# Calibration.net
KiCad netlist of a schematic drawn in EAGLE
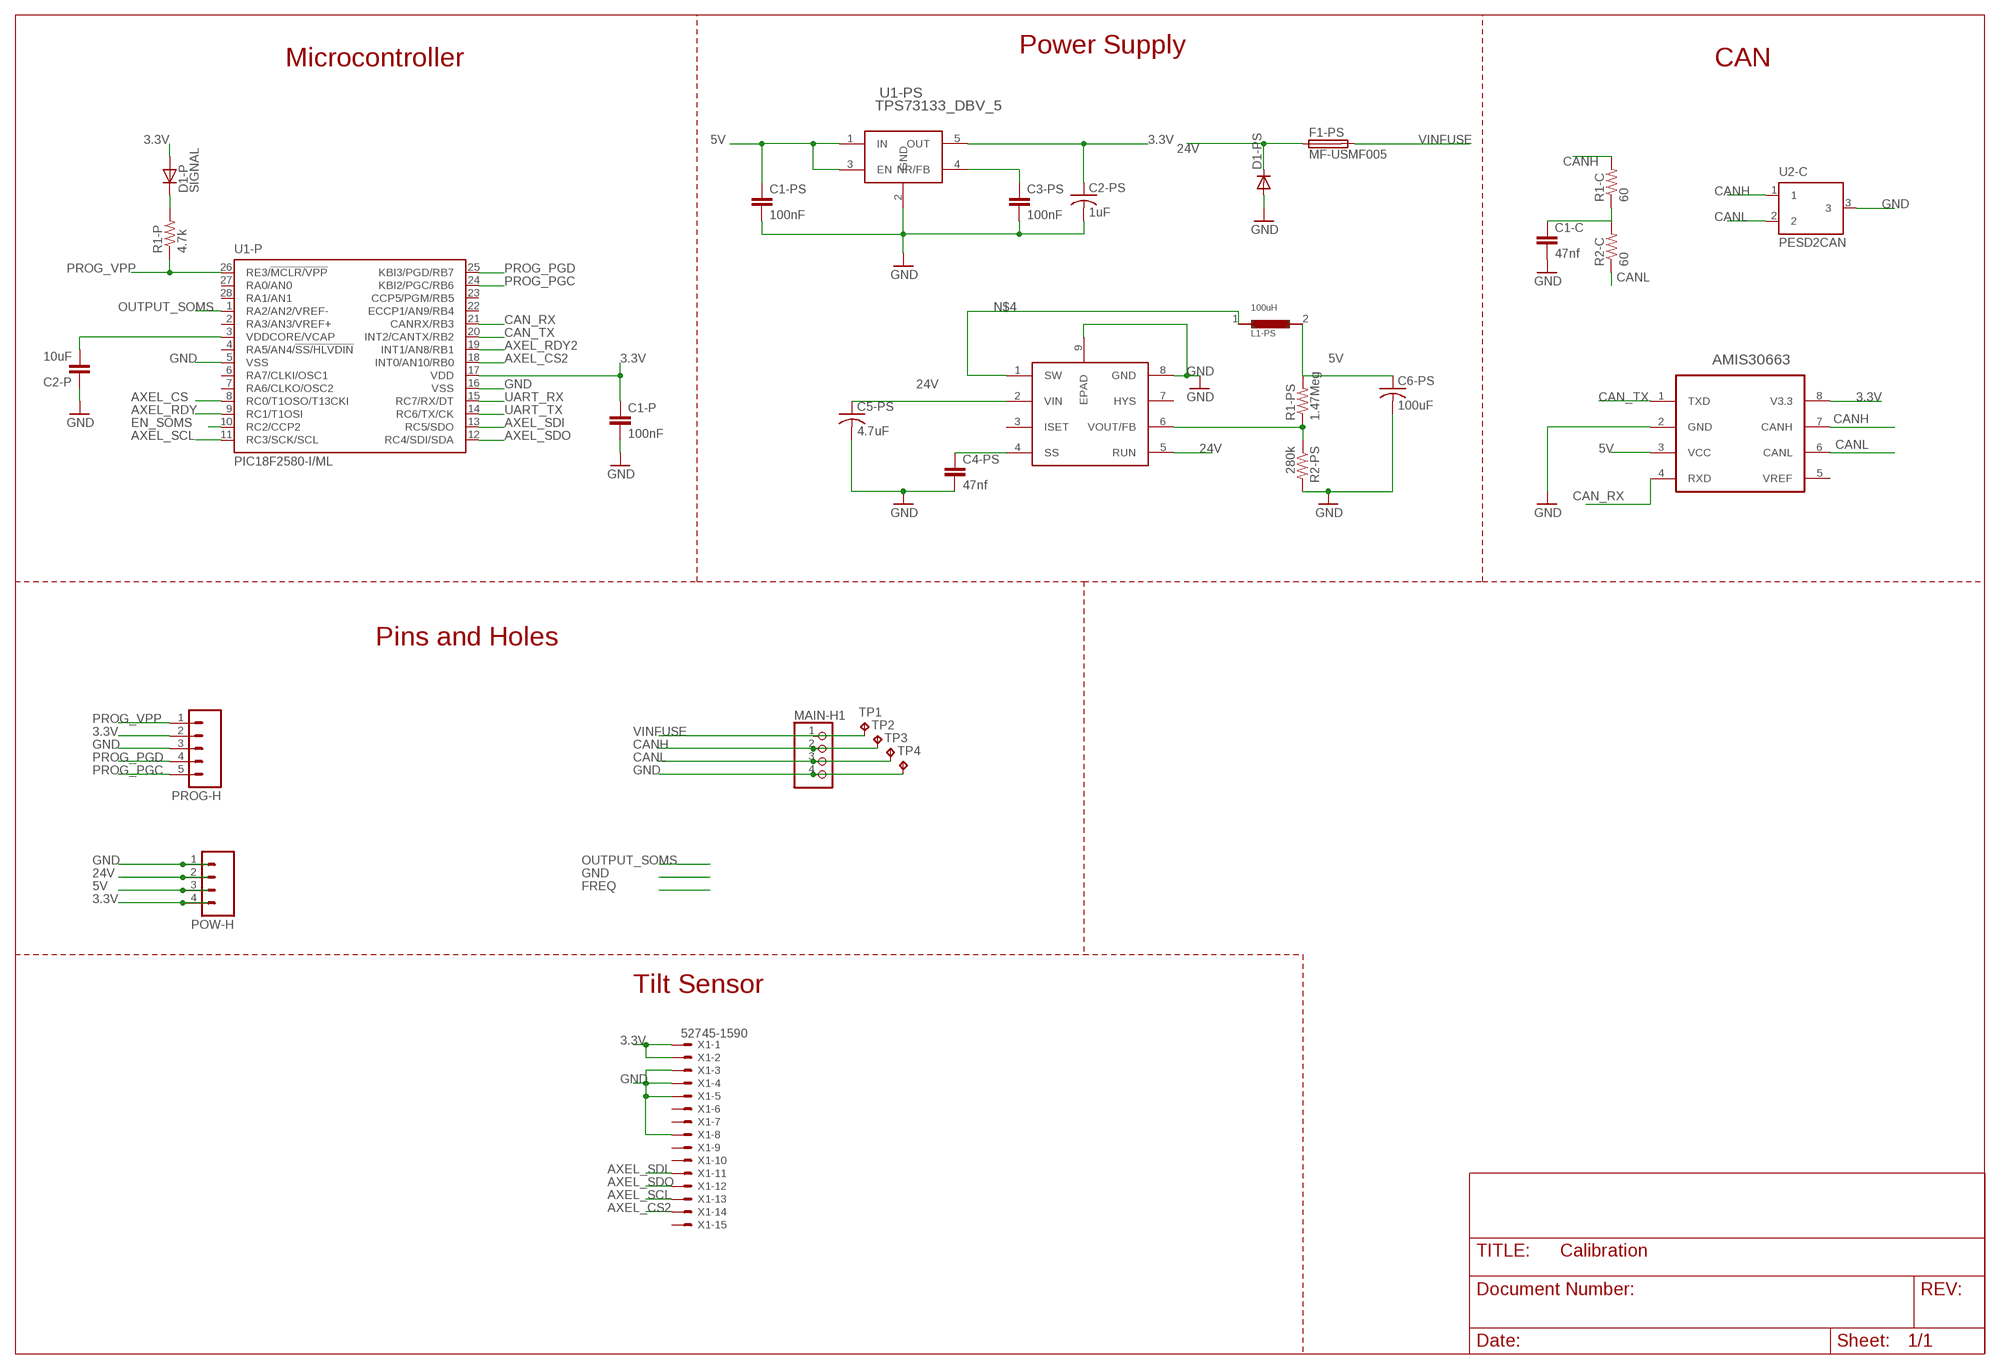
[diagram p0: schematic, sheet 1]

(export (version "E")
  (design (tool "Eeschema 10.0.6"))
  (components
    (comp (ref "C1-C")
      (value "47nf")
      (footprint "eagle-import:C0805")
      (libsource (lib "eagle-import") (part "C-EUC0805"))
    )
    (comp (ref "C1-P")
      (value "100nF")
      (footprint "eagle-import:C0603")
      (libsource (lib "eagle-import") (part "resistor_C-EUC0603"))
    )
    (comp (ref "C1-PS")
      (value "100nF")
      (footprint "eagle-import:C0603")
      (libsource (lib "eagle-import") (part "C-EUC0603"))
    )
    (comp (ref "C2-P")
      (value "10uF")
      (footprint "eagle-import:C0603")
      (libsource (lib "eagle-import") (part "C-EUC0603"))
    )
    (comp (ref "C2-PS")
      (value "1uF")
      (footprint "eagle-import:C0402")
      (libsource (lib "eagle-import") (part "C-USC0402"))
    )
    (comp (ref "C3-PS")
      (value "100nF")
      (footprint "eagle-import:C0603")
      (libsource (lib "eagle-import") (part "C-EUC0603"))
    )
    (comp (ref "C4-PS")
      (value "47nf")
      (footprint "eagle-import:C0805")
      (libsource (lib "eagle-import") (part "C-EUC0805"))
    )
    (comp (ref "C5-PS")
      (value "4.7uF")
      (footprint "eagle-import:C1206K")
      (libsource (lib "eagle-import") (part "C-USC1206K"))
    )
    (comp (ref "C6-PS")
      (value "100uF")
      (footprint "eagle-import:C1210K")
      (libsource (lib "eagle-import") (part "C-USC1210K"))
    )
    (comp (ref "D1-P")
      (value "SIGNAL")
      (footprint "eagle-import:DIODE-0603")
      (libsource (lib "eagle-import") (part "DIODE0603"))
    )
    (comp (ref "D1-PS")
      (value "DIODE-DO-214AC")
      (footprint "eagle-import:DO-214AC")
      (libsource (lib "eagle-import") (part "DIODE-DO-214AC"))
    )
    (comp (ref "F1-PS")
      (value "MF-USMF005")
      (footprint "eagle-import:1210")
      (libsource (lib "eagle-import") (part "MF-USMF075"))
    )
    (comp (ref "L1-PS")
      (value "100uH")
      (footprint "eagle-import:1210")
      (libsource (lib "eagle-import") (part "LQH32PN101MN0L"))
    )
    (comp (ref "MAIN-H1")
      (value "PINHD-1X04_2.54")
      (footprint "eagle-import:1X04")
      (libsource (lib "eagle-import") (part "PINHD-1X04_2.54"))
    )
    (comp (ref "POW-H")
      (value "M041X04_NO_SILK")
      (footprint "eagle-import:1X04_NO_SILK")
      (libsource (lib "eagle-import") (part "M041X04_NO_SILK"))
    )
    (comp (ref "PROG-H")
      (value "M05PTH")
      (footprint "eagle-import:1X05")
      (libsource (lib "eagle-import") (part "M05PTH"))
    )
    (comp (ref "R1-C")
      (value "60")
      (footprint "eagle-import:R0805")
      (libsource (lib "eagle-import") (part "R-US_R0805"))
    )
    (comp (ref "R1-P")
      (value "4.7k")
      (footprint "eagle-import:R0603")
      (libsource (lib "eagle-import") (part "resistor_R-US_R0603"))
    )
    (comp (ref "R1-PS")
      (value "1.47Meg")
      (footprint "eagle-import:R0805")
      (libsource (lib "eagle-import") (part "R-US_R0805"))
    )
    (comp (ref "R2-C")
      (value "60")
      (footprint "eagle-import:R0805")
      (libsource (lib "eagle-import") (part "R-US_R0805"))
    )
    (comp (ref "R2-PS")
      (value "280k")
      (footprint "eagle-import:R0805")
      (libsource (lib "eagle-import") (part "R-US_R0805"))
    )
    (comp (ref "TP1")
      (value "TPTP10SQ")
      (footprint "eagle-import:TP10SQ")
      (libsource (lib "eagle-import") (part "TPTP10SQ"))
    )
    (comp (ref "TP2")
      (value "TPTP10SQ")
      (footprint "eagle-import:TP10SQ")
      (libsource (lib "eagle-import") (part "TPTP10SQ"))
    )
    (comp (ref "TP3")
      (value "TPTP10SQ")
      (footprint "eagle-import:TP10SQ")
      (libsource (lib "eagle-import") (part "TPTP10SQ"))
    )
    (comp (ref "TP4")
      (value "TPTP10SQ")
      (footprint "eagle-import:TP10SQ")
      (libsource (lib "eagle-import") (part "TPTP10SQ"))
    )
    (comp (ref "U1-P")
      (value "PIC18F2580-I/ML")
      (footprint "eagle-import:QFN28-ML_6X6MM")
      (fields (field (name "MF") "MICROCHIP"))
      (libsource (lib "eagle-import") (part "PIC18F280-I/ML5"))
    )
    (comp (ref "U1-PS")
      (value "TPS73133_DBV_5")
      (footprint "eagle-import:DBV5")
      (fields
        (field (name "GENERIC_PART_NUMBER") "TPS73133")
        (field (name "MANUFACTURER") "Texas Instruments")
        (field (name "MANUFACTURER_PART_NUMBER") "tps73133_dbv_5")
      )
      (libsource (lib "eagle-import") (part "TPS73133_DBV_5"))
    )
    (comp (ref "U2")
      (value "AMIS30663CAN")
      (footprint "eagle-import:SOIC8")
      (fields (field (name "MPN") "AMIS30663"))
      (libsource (lib "eagle-import") (part "AMIS30663CAN"))
    )
    (comp (ref "U2-C")
      (value "PESD2CAN")
      (footprint "eagle-import:SOT23")
      (libsource (lib "eagle-import") (part "PESD2CAN"))
    )
    (comp (ref "U2-PS")
      (value "LTC3631-5")
      (footprint "eagle-import:MSOP8E")
      (libsource (lib "eagle-import") (part "LTC3631"))
    )
    (comp (ref "X1")
      (value "52745-1590")
      (footprint "eagle-import:52745-1590")
      (fields (field (name "MF") "MOLEX"))
      (libsource (lib "eagle-import") (part "52745-1590"))
    )
  )
  (nets
    (net (code "1") (name "/3.3V") (class "Default")
      (node (ref "C1-P") (pin "1") (pinfunction "1_1") (pintype "passive"))
      (node (ref "C2-PS") (pin "1") (pinfunction "1_1") (pintype "passive"))
      (node (ref "D1-P") (pin "A") (pinfunction "A_A") (pintype "passive"))
      (node (ref "POW-H") (pin "4") (pinfunction "4_4") (pintype "passive"))
      (node (ref "PROG-H") (pin "2") (pinfunction "2_2") (pintype "passive"))
      (node (ref "U1-P") (pin "17") (pinfunction "VDD_17") (pintype "power_in"))
      (node (ref "U1-PS") (pin "5") (pinfunction "OUT_5") (pintype "output"))
      (node (ref "U2") (pin "8") (pinfunction "V3.3_8") (pintype "bidirectional"))
      (node (ref "X1") (pin "1") (pinfunction "S_1") (pintype "passive"))
      (node (ref "X1") (pin "2") (pinfunction "S_2") (pintype "passive"))
    )
    (net (code "2") (name "/5V") (class "Default")
      (node (ref "C1-PS") (pin "1") (pinfunction "1_1") (pintype "passive"))
      (node (ref "C6-PS") (pin "1") (pinfunction "1_1") (pintype "passive"))
      (node (ref "L1-PS") (pin "2") (pinfunction "2_2") (pintype "bidirectional"))
      (node (ref "POW-H") (pin "3") (pinfunction "3_3") (pintype "passive"))
      (node (ref "R1-PS") (pin "2") (pinfunction "2_2") (pintype "passive"))
      (node (ref "U1-PS") (pin "1") (pinfunction "IN_1") (pintype "input"))
      (node (ref "U1-PS") (pin "3") (pinfunction "EN_3") (pintype "passive"))
      (node (ref "U2") (pin "3") (pinfunction "VCC_3") (pintype "bidirectional"))
    )
    (net (code "3") (name "/24V") (class "Default")
      (node (ref "C5-PS") (pin "1") (pinfunction "1_1") (pintype "passive"))
      (node (ref "D1-PS") (pin "1") (pinfunction "C_1") (pintype "passive"))
      (node (ref "F1-PS") (pin "1") (pinfunction "1_1") (pintype "passive"))
      (node (ref "POW-H") (pin "2") (pinfunction "2_2") (pintype "passive"))
      (node (ref "U2-PS") (pin "2") (pinfunction "VIN_2") (pintype "bidirectional"))
      (node (ref "U2-PS") (pin "5") (pinfunction "RUN_5") (pintype "bidirectional"))
    )
    (net (code "4") (name "/AXEL_CS") (class "Default")
      (node (ref "U1-P") (pin "8") (pinfunction "RC0/T1OSO/T13CKI_8") (pintype "bidirectional"))
    )
    (net (code "5") (name "/AXEL_CS2") (class "Default")
      (node (ref "U1-P") (pin "18") (pinfunction "INT0/AN10/RB0_18") (pintype "bidirectional"))
      (node (ref "X1") (pin "14") (pinfunction "S_14") (pintype "passive"))
    )
    (net (code "6") (name "/AXEL_RDY") (class "Default")
      (node (ref "U1-P") (pin "9") (pinfunction "RC1/T1OSI_9") (pintype "bidirectional"))
    )
    (net (code "7") (name "/AXEL_RDY2") (class "Default")
      (node (ref "U1-P") (pin "19") (pinfunction "INT1/AN8/RB1_19") (pintype "bidirectional"))
    )
    (net (code "8") (name "/AXEL_SCL") (class "Default")
      (node (ref "U1-P") (pin "11") (pinfunction "RC3/SCK/SCL_11") (pintype "bidirectional"))
      (node (ref "X1") (pin "13") (pinfunction "S_13") (pintype "passive"))
    )
    (net (code "9") (name "/AXEL_SDI") (class "Default")
      (node (ref "U1-P") (pin "13") (pinfunction "RC5/SDO_13") (pintype "bidirectional"))
      (node (ref "X1") (pin "11") (pinfunction "S_11") (pintype "passive"))
    )
    (net (code "10") (name "/AXEL_SDO") (class "Default")
      (node (ref "U1-P") (pin "12") (pinfunction "RC4/SDI/SDA_12") (pintype "bidirectional"))
      (node (ref "X1") (pin "12") (pinfunction "S_12") (pintype "passive"))
    )
    (net (code "11") (name "/CANH") (class "Default")
      (node (ref "MAIN-H1") (pin "2") (pinfunction "2_2") (pintype "passive"))
      (node (ref "R1-C") (pin "2") (pinfunction "2_2") (pintype "passive"))
      (node (ref "TP2") (pin "TP") (pinfunction "TP_TP") (pintype "input"))
      (node (ref "U2") (pin "7") (pinfunction "CANH_7") (pintype "bidirectional"))
      (node (ref "U2-C") (pin "1") (pinfunction "1_1") (pintype "input"))
    )
    (net (code "12") (name "/CANL") (class "Default")
      (node (ref "MAIN-H1") (pin "3") (pinfunction "3_3") (pintype "passive"))
      (node (ref "R2-C") (pin "1") (pinfunction "1_1") (pintype "passive"))
      (node (ref "TP3") (pin "TP") (pinfunction "TP_TP") (pintype "input"))
      (node (ref "U2") (pin "6") (pinfunction "CANL_6") (pintype "bidirectional"))
      (node (ref "U2-C") (pin "2") (pinfunction "2_2") (pintype "power_in"))
    )
    (net (code "13") (name "/CAN_RX") (class "Default")
      (node (ref "U1-P") (pin "21") (pinfunction "CANRX/RB3_21") (pintype "bidirectional"))
      (node (ref "U2") (pin "4") (pinfunction "RXD_4") (pintype "bidirectional"))
    )
    (net (code "14") (name "/CAN_TX") (class "Default")
      (node (ref "U1-P") (pin "20") (pinfunction "INT2/CANTX/RB2_20") (pintype "bidirectional"))
      (node (ref "U2") (pin "1") (pinfunction "TXD_1") (pintype "bidirectional"))
    )
    (net (code "15") (name "/EN_SOMS") (class "Default")
      (node (ref "U1-P") (pin "10") (pinfunction "RC2/CCP2_10") (pintype "bidirectional"))
    )
    (net (code "17") (name "/N$4") (class "Default")
      (node (ref "L1-PS") (pin "1") (pinfunction "1_1") (pintype "bidirectional"))
      (node (ref "U2-PS") (pin "1") (pinfunction "SW_1") (pintype "bidirectional"))
    )
    (net (code "18") (name "/OUTPUT_SOMS") (class "Default")
      (node (ref "U1-P") (pin "1") (pinfunction "RA2/AN2/VREF-_1") (pintype "bidirectional"))
    )
    (net (code "19") (name "/PROG_PGC") (class "Default")
      (node (ref "PROG-H") (pin "5") (pinfunction "5_5") (pintype "passive"))
      (node (ref "U1-P") (pin "24") (pinfunction "KBI2/PGC/RB6_24") (pintype "bidirectional"))
    )
    (net (code "20") (name "/PROG_PGD") (class "Default")
      (node (ref "PROG-H") (pin "4") (pinfunction "4_4") (pintype "passive"))
      (node (ref "U1-P") (pin "25") (pinfunction "KBI3/PGD/RB7_25") (pintype "bidirectional"))
    )
    (net (code "21") (name "/PROG_VPP") (class "Default")
      (node (ref "PROG-H") (pin "1") (pinfunction "1_1") (pintype "passive"))
      (node (ref "R1-P") (pin "1") (pinfunction "1_1") (pintype "passive"))
      (node (ref "U1-P") (pin "26") (pinfunction "RE3/~{MCLR/VPP}_26") (pintype "input"))
    )
    (net (code "22") (name "/UART_RX") (class "Default")
      (node (ref "U1-P") (pin "15") (pinfunction "RC7/RX/DT_15") (pintype "bidirectional"))
    )
    (net (code "23") (name "/UART_TX") (class "Default")
      (node (ref "U1-P") (pin "14") (pinfunction "RC6/TX/CK_14") (pintype "bidirectional"))
    )
    (net (code "24") (name "/VINFUSE") (class "Default")
      (node (ref "F1-PS") (pin "2") (pinfunction "2_2") (pintype "passive"))
      (node (ref "MAIN-H1") (pin "1") (pinfunction "1_1") (pintype "passive"))
      (node (ref "TP1") (pin "TP") (pinfunction "TP_TP") (pintype "input"))
    )
    (net (code "25") (name "GND") (class "Default")
      (node (ref "C1-C") (pin "2") (pinfunction "2_2") (pintype "passive"))
      (node (ref "C1-P") (pin "2") (pinfunction "2_2") (pintype "passive"))
      (node (ref "C1-PS") (pin "2") (pinfunction "2_2") (pintype "passive"))
      (node (ref "C2-P") (pin "1") (pinfunction "1_1") (pintype "passive"))
      (node (ref "C2-PS") (pin "2") (pinfunction "2_2") (pintype "passive"))
      (node (ref "C3-PS") (pin "2") (pinfunction "2_2") (pintype "passive"))
      (node (ref "C4-PS") (pin "2") (pinfunction "2_2") (pintype "passive"))
      (node (ref "C5-PS") (pin "2") (pinfunction "2_2") (pintype "passive"))
      (node (ref "C6-PS") (pin "2") (pinfunction "2_2") (pintype "passive"))
      (node (ref "D1-PS") (pin "2") (pinfunction "A_2") (pintype "passive"))
      (node (ref "MAIN-H1") (pin "4") (pinfunction "4_4") (pintype "passive"))
      (node (ref "POW-H") (pin "1") (pinfunction "1_1") (pintype "passive"))
      (node (ref "PROG-H") (pin "3") (pinfunction "3_3") (pintype "passive"))
      (node (ref "R2-PS") (pin "2") (pinfunction "2_2") (pintype "passive"))
      (node (ref "TP4") (pin "TP") (pinfunction "TP_TP") (pintype "input"))
      (node (ref "U1-P") (pin "16") (pinfunction "VSS_16") (pintype "power_in"))
      (node (ref "U1-P") (pin "5") (pinfunction "VSS_5") (pintype "power_in"))
      (node (ref "U1-PS") (pin "2") (pinfunction "GND_2") (pintype "power_in"))
      (node (ref "U2") (pin "2") (pinfunction "GND_2") (pintype "bidirectional"))
      (node (ref "U2-C") (pin "3") (pinfunction "3_3") (pintype "output"))
      (node (ref "U2-PS") (pin "8") (pinfunction "GND_8") (pintype "bidirectional"))
      (node (ref "U2-PS") (pin "9") (pinfunction "EPAD_9") (pintype "bidirectional"))
      (node (ref "X1") (pin "3") (pinfunction "S_3") (pintype "passive"))
      (node (ref "X1") (pin "4") (pinfunction "S_4") (pintype "passive"))
      (node (ref "X1") (pin "5") (pinfunction "S_5") (pintype "passive"))
      (node (ref "X1") (pin "8") (pinfunction "S_8") (pintype "passive"))
    )
    (net (code "26") (name "Net-(C1-C-Pad1)") (class "Default")
      (node (ref "C1-C") (pin "1") (pinfunction "1_1") (pintype "passive"))
      (node (ref "R1-C") (pin "1") (pinfunction "1_1") (pintype "passive"))
      (node (ref "R2-C") (pin "2") (pinfunction "2_2") (pintype "passive"))
    )
    (net (code "27") (name "Net-(D1-P-PadC)") (class "Default")
      (node (ref "D1-P") (pin "C") (pinfunction "C_C") (pintype "passive"))
      (node (ref "R1-P") (pin "2") (pinfunction "2_2") (pintype "passive"))
    )
    (net (code "28") (name "Net-(U1-P-VDDCORE{slash}VCAP)") (class "Default")
      (node (ref "C2-P") (pin "2") (pinfunction "2_2") (pintype "passive"))
      (node (ref "U1-P") (pin "3") (pinfunction "VDDCORE/VCAP_3") (pintype "bidirectional"))
    )
    (net (code "29") (name "Net-(U1-PS-NR{slash}FB)") (class "Default")
      (node (ref "C3-PS") (pin "1") (pinfunction "1_1") (pintype "passive"))
      (node (ref "U1-PS") (pin "4") (pinfunction "NR/FB_4") (pintype "passive"))
    )
    (net (code "30") (name "Net-(U2-PS-SS)") (class "Default")
      (node (ref "C4-PS") (pin "1") (pinfunction "1_1") (pintype "passive"))
      (node (ref "U2-PS") (pin "4") (pinfunction "SS_4") (pintype "bidirectional"))
    )
    (net (code "31") (name "Net-(U2-PS-VOUT{slash}FB)") (class "Default")
      (node (ref "R1-PS") (pin "1") (pinfunction "1_1") (pintype "passive"))
      (node (ref "R2-PS") (pin "1") (pinfunction "1_1") (pintype "passive"))
      (node (ref "U2-PS") (pin "6") (pinfunction "VOUT/FB_6") (pintype "bidirectional"))
    )
    (net (code "32") (name "unconnected-(U1-P-CCP5{slash}PGM{slash}RB5-Pad23)") (class "Default")
      (node (ref "U1-P") (pin "23") (pinfunction "CCP5/PGM/RB5_23") (pintype "bidirectional"))
    )
    (net (code "33") (name "unconnected-(U1-P-ECCP1{slash}AN9{slash}RB4-Pad22)") (class "Default")
      (node (ref "U1-P") (pin "22") (pinfunction "ECCP1/AN9/RB4_22") (pintype "bidirectional"))
    )
    (net (code "34") (name "unconnected-(U1-P-RA0{slash}AN0-Pad27)") (class "Default")
      (node (ref "U1-P") (pin "27") (pinfunction "RA0/AN0_27") (pintype "bidirectional"))
    )
    (net (code "35") (name "unconnected-(U1-P-RA1{slash}AN1-Pad28)") (class "Default")
      (node (ref "U1-P") (pin "28") (pinfunction "RA1/AN1_28") (pintype "bidirectional"))
    )
    (net (code "36") (name "unconnected-(U1-P-RA3{slash}AN3{slash}VREF+-Pad2)") (class "Default")
      (node (ref "U1-P") (pin "2") (pinfunction "RA3/AN3/VREF+_2") (pintype "bidirectional"))
    )
    (net (code "37") (name "unconnected-(U1-P-RA5{slash}AN4{slash}~{SS{slash}HLVDIN}-Pad4)") (class "Default")
      (node (ref "U1-P") (pin "4") (pinfunction "RA5/AN4/~{SS/HLVDIN}_4") (pintype "bidirectional"))
    )
    (net (code "38") (name "unconnected-(U1-P-RA6{slash}CLKO{slash}OSC2-Pad7)") (class "Default")
      (node (ref "U1-P") (pin "7") (pinfunction "RA6/CLKO/OSC2_7") (pintype "output"))
    )
    (net (code "39") (name "unconnected-(U1-P-RA7{slash}CLKI{slash}OSC1-Pad6)") (class "Default")
      (node (ref "U1-P") (pin "6") (pinfunction "RA7/CLKI/OSC1_6") (pintype "input"))
    )
    (net (code "40") (name "unconnected-(U2-PS-HYS-Pad7)") (class "Default")
      (node (ref "U2-PS") (pin "7") (pinfunction "HYS_7") (pintype "bidirectional"))
    )
    (net (code "41") (name "unconnected-(U2-PS-ISET-Pad3)") (class "Default")
      (node (ref "U2-PS") (pin "3") (pinfunction "ISET_3") (pintype "bidirectional"))
    )
    (net (code "42") (name "unconnected-(U2-VREF-Pad5)") (class "Default")
      (node (ref "U2") (pin "5") (pinfunction "VREF_5") (pintype "bidirectional"))
    )
    (net (code "43") (name "unconnected-(X1B-S-Pad10)") (class "Default")
      (node (ref "X1") (pin "10") (pinfunction "S_10") (pintype "passive"))
    )
    (net (code "44") (name "unconnected-(X1G-S-Pad15)") (class "Default")
      (node (ref "X1") (pin "15") (pinfunction "S_15") (pintype "passive"))
    )
    (net (code "45") (name "unconnected-(X1L-S-Pad6)") (class "Default")
      (node (ref "X1") (pin "6") (pinfunction "S_6") (pintype "passive"))
    )
    (net (code "46") (name "unconnected-(X1M-S-Pad7)") (class "Default")
      (node (ref "X1") (pin "7") (pinfunction "S_7") (pintype "passive"))
    )
    (net (code "47") (name "unconnected-(X1O-S-Pad9)") (class "Default")
      (node (ref "X1") (pin "9") (pinfunction "S_9") (pintype "passive"))
    )
  )
)
